# Midas.net
KiCad netlist of a schematic drawn in Altium Designer
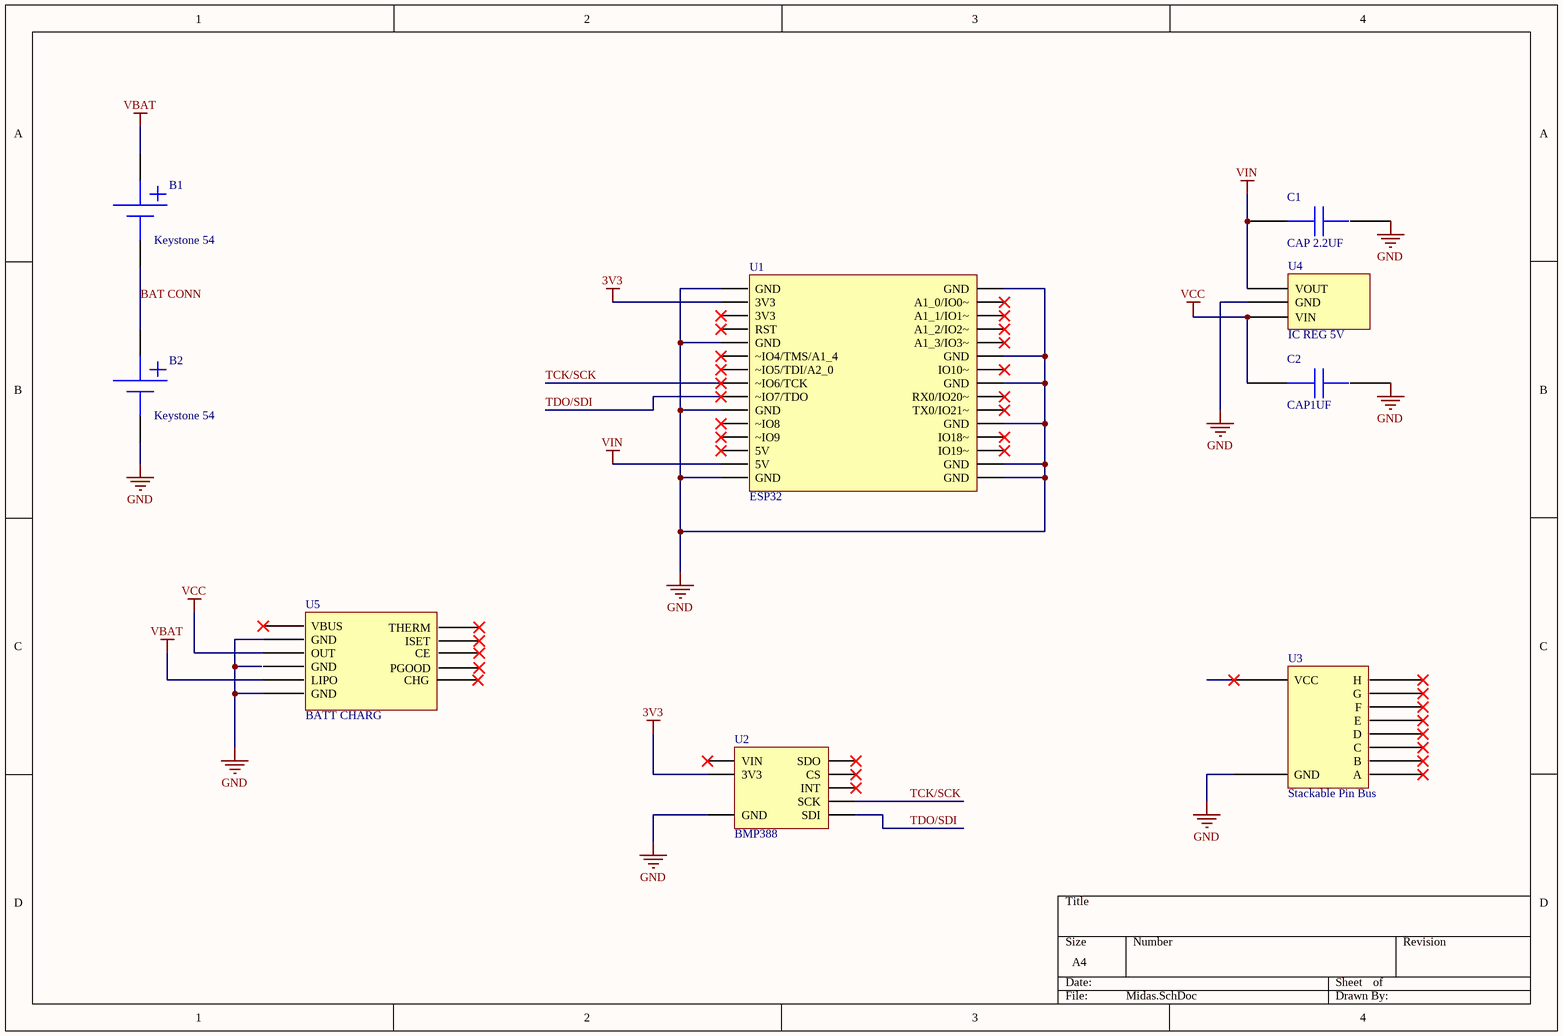
[diagram p0: Midas.SchDoc]

(export (version "E")
  (design (tool "Eeschema 10.0.6"))
  (components
    (comp (ref "B1")
      (value "Keystone 54")
      (footprint "Keystone 54")
      (description "Batteries/Accessories\r\nBATT CONT CLIP 18650 1CEL PC PIN")
      (fields
        (field (name "MANUFACTURER") "Keystone Electronics")
        (field (name "MANUFACTURER PART NUMBER") "54")
      )
      (libsource (lib "Midas") (part "54"))
    )
    (comp (ref "B2")
      (value "Keystone 54")
      (footprint "Keystone 54")
      (description "Batteries/Accessories\r\nBATT CONT CLIP 18650 1CEL PC PIN")
      (fields
        (field (name "MANUFACTURER") "Keystone Electronics")
        (field (name "MANUFACTURER PART NUMBER") "54")
      )
      (libsource (lib "Midas") (part "54"))
    )
    (comp (ref "C1")
      (value "CAP 2.2UF")
      (footprint "FA16X7R1E225KNU06")
      (fields
        (field (name "MANUFACTURER") "TDK")
        (field (name "MANUFACTURER PART NUMBER") "FA16X7R1E225KNU06")
      )
      (libsource (lib "Midas") (part "FA16X7R1E225KNU06"))
    )
    (comp (ref "C2")
      (value "CAP1UF")
      (footprint "C330C105K5R5TA7301")
      (fields
        (field (name "MANUFACTURER") "KEMET")
        (field (name "MANUFACTURER PART NUMBER") "C330C105K5R5TA7301")
      )
      (libsource (lib "Midas") (part "C330C105K5R5TA7301"))
    )
    (comp (ref "U1")
      (value "ESP32")
      (footprint "ESP32")
      (fields
        (field (name "MANUFACTURER") "Espressif Systems")
        (field (name "MANUFACTURER PART NUMBER") "ESP32-C3-DEVKITC-02")
      )
      (libsource (lib "Midas") (part "ESP32-C3-DEVKITC-02"))
    )
    (comp (ref "U2")
      (value "BMP388")
      (footprint "3966")
      (fields
        (field (name "MANUFACTURER") "Adafruit Industries")
        (field (name "MANUFACTURER PART NUMBER") "3966")
      )
      (libsource (lib "Midas") (part "3966"))
    )
    (comp (ref "U3")
      (value "Stackable Pin Bus")
      (footprint "STACKABLE_PIN_BUS")
      (description "10 pinos, Passo 2.54mm, Dimensões da barra 26x2x8mm")
      (libsource (lib "Midas") (part "Barramento Empilhável"))
    )
    (comp (ref "U4")
      (value "IC REG 5V")
      (footprint "AP7381-50V-A")
      (description "Fixed Positive LDO Regulator")
      (fields (field (name "MANUFACTURER") "Diodes") (field (name "MANUFACTURER PART NUMBER") "AP7381-50V-A"))
      (libsource (lib "Midas") (part "AP7381-50V-A"))
    )
    (comp (ref "U5")
      (value "BATT CHARG")
      (footprint "4755")
      (fields
        (field (name "MANUFACTURER") "Adafruit Industries")
        (field (name "MANUFACTURER PART NUMBER") "4755")
      )
      (libsource (lib "Midas") (part "4755"))
    )
  )
  (nets
    (net (code "1") (name "/BAT CONN") (class "Default")
      (node (ref "B1") (pin "2") (pinfunction "NEG_2") (pintype "passive"))
      (node (ref "B2") (pin "1") (pinfunction "POS_1") (pintype "passive"))
    )
    (net (code "2") (name "/TCK{slash}SCK") (class "Default")
      (node (ref "U1") (pin "8") (pinfunction "~IO6/TCK_8") (pintype "passive"))
      (node (ref "U2") (pin "4") (pinfunction "SCK_4") (pintype "passive"))
    )
    (net (code "3") (name "/TDO{slash}SDI") (class "Default")
      (node (ref "U1") (pin "9") (pinfunction "~IO7/TDO_9") (pintype "passive"))
      (node (ref "U2") (pin "6") (pinfunction "SDI_6") (pintype "passive"))
    )
    (net (code "4") (name "3V3") (class "Default")
      (node (ref "U1") (pin "2") (pinfunction "3V3_2") (pintype "passive"))
      (node (ref "U2") (pin "2") (pinfunction "3V3_2") (pintype "passive"))
    )
    (net (code "5") (name "GND") (class "Default")
      (node (ref "B2") (pin "2") (pinfunction "NEG_2") (pintype "passive"))
      (node (ref "C1") (pin "2") (pinfunction "2_2") (pintype "passive"))
      (node (ref "C2") (pin "2") (pinfunction "2_2") (pintype "passive"))
      (node (ref "U1") (pin "1") (pinfunction "GND_1") (pintype "passive"))
      (node (ref "U1") (pin "10") (pinfunction "GND_10") (pintype "passive"))
      (node (ref "U1") (pin "15") (pinfunction "GND_15") (pintype "passive"))
      (node (ref "U1") (pin "16") (pinfunction "GND_16") (pintype "passive"))
      (node (ref "U1") (pin "17") (pinfunction "GND_17") (pintype "passive"))
      (node (ref "U1") (pin "20") (pinfunction "GND_20") (pintype "passive"))
      (node (ref "U1") (pin "23") (pinfunction "GND_23") (pintype "passive"))
      (node (ref "U1") (pin "25") (pinfunction "GND_25") (pintype "passive"))
      (node (ref "U1") (pin "30") (pinfunction "GND_30") (pintype "passive"))
      (node (ref "U1") (pin "5") (pinfunction "GND_5") (pintype "passive"))
      (node (ref "U2") (pin "3") (pinfunction "GND_3") (pintype "passive"))
      (node (ref "U3") (pin "2") (pinfunction "GND_2") (pintype "passive"))
      (node (ref "U4") (pin "2") (pinfunction "GND_2") (pintype "passive"))
      (node (ref "U5") (pin "11") (pinfunction "GND_11") (pintype "passive"))
      (node (ref "U5") (pin "2") (pinfunction "GND_2") (pintype "passive"))
    )
    (net (code "6") (name "VBAT") (class "Default")
      (node (ref "B1") (pin "1") (pinfunction "POS_1") (pintype "passive"))
      (node (ref "U5") (pin "10") (pinfunction "LIPO_10") (pintype "passive"))
    )
    (net (code "7") (name "VCC") (class "Default")
      (node (ref "C2") (pin "1") (pinfunction "1_1") (pintype "passive"))
      (node (ref "U4") (pin "3") (pinfunction "VIN_3") (pintype "passive"))
      (node (ref "U5") (pin "8") (pinfunction "OUT_8") (pintype "passive"))
    )
    (net (code "8") (name "VIN") (class "Default")
      (node (ref "C1") (pin "1") (pinfunction "1_1") (pintype "passive"))
      (node (ref "U1") (pin "14") (pinfunction "5V_14") (pintype "passive"))
      (node (ref "U4") (pin "1") (pinfunction "VOUT_1") (pintype "passive"))
    )
    (net (code "9") (name "unconnected-(U1-3V3-Pad3)") (class "Default")
      (node (ref "U1") (pin "3") (pinfunction "3V3_3") (pintype "passive+no_connect"))
    )
    (net (code "10") (name "unconnected-(U1-5V-Pad13)") (class "Default")
      (node (ref "U1") (pin "13") (pinfunction "5V_13") (pintype "passive+no_connect"))
    )
    (net (code "11") (name "unconnected-(U1-A1_0{slash}IO0~-Pad29)") (class "Default")
      (node (ref "U1") (pin "29") (pinfunction "A1_0/IO0~_29") (pintype "passive+no_connect"))
    )
    (net (code "12") (name "unconnected-(U1-A1_1{slash}IO1~-Pad28)") (class "Default")
      (node (ref "U1") (pin "28") (pinfunction "A1_1/IO1~_28") (pintype "passive+no_connect"))
    )
    (net (code "13") (name "unconnected-(U1-A1_2{slash}IO2~-Pad27)") (class "Default")
      (node (ref "U1") (pin "27") (pinfunction "A1_2/IO2~_27") (pintype "passive+no_connect"))
    )
    (net (code "14") (name "unconnected-(U1-A1_3{slash}IO3~-Pad26)") (class "Default")
      (node (ref "U1") (pin "26") (pinfunction "A1_3/IO3~_26") (pintype "passive+no_connect"))
    )
    (net (code "15") (name "unconnected-(U1-IO10~-Pad24)") (class "Default")
      (node (ref "U1") (pin "24") (pinfunction "IO10~_24") (pintype "passive+no_connect"))
    )
    (net (code "16") (name "unconnected-(U1-IO18~-Pad19)") (class "Default")
      (node (ref "U1") (pin "19") (pinfunction "IO18~_19") (pintype "passive+no_connect"))
    )
    (net (code "17") (name "unconnected-(U1-IO19~-Pad18)") (class "Default")
      (node (ref "U1") (pin "18") (pinfunction "IO19~_18") (pintype "passive+no_connect"))
    )
    (net (code "18") (name "unconnected-(U1-RST-Pad4)") (class "Default")
      (node (ref "U1") (pin "4") (pinfunction "RST_4") (pintype "passive+no_connect"))
    )
    (net (code "19") (name "unconnected-(U1-RX0{slash}IO20~-Pad22)") (class "Default")
      (node (ref "U1") (pin "22") (pinfunction "RX0/IO20~_22") (pintype "passive+no_connect"))
    )
    (net (code "20") (name "unconnected-(U1-TX0{slash}IO21~-Pad21)") (class "Default")
      (node (ref "U1") (pin "21") (pinfunction "TX0/IO21~_21") (pintype "passive+no_connect"))
    )
    (net (code "21") (name "unconnected-(U1-~IO4{slash}TMS{slash}A1_4-Pad6)") (class "Default")
      (node (ref "U1") (pin "6") (pinfunction "~IO4/TMS/A1_4_6") (pintype "passive+no_connect"))
    )
    (net (code "22") (name "unconnected-(U1-~IO5{slash}TDI{slash}A2_0-Pad7)") (class "Default")
      (node (ref "U1") (pin "7") (pinfunction "~IO5/TDI/A2_0_7") (pintype "passive+no_connect"))
    )
    (net (code "23") (name "unconnected-(U1-~IO8-Pad11)") (class "Default")
      (node (ref "U1") (pin "11") (pinfunction "~IO8_11") (pintype "passive+no_connect"))
    )
    (net (code "24") (name "unconnected-(U1-~IO9-Pad12)") (class "Default")
      (node (ref "U1") (pin "12") (pinfunction "~IO9_12") (pintype "passive+no_connect"))
    )
    (net (code "25") (name "unconnected-(U2-CS-Pad7)") (class "Default")
      (node (ref "U2") (pin "7") (pinfunction "CS_7") (pintype "passive+no_connect"))
    )
    (net (code "26") (name "unconnected-(U2-INT-Pad8)") (class "Default")
      (node (ref "U2") (pin "8") (pinfunction "INT_8") (pintype "passive+no_connect"))
    )
    (net (code "27") (name "unconnected-(U2-SDO-Pad5)") (class "Default")
      (node (ref "U2") (pin "5") (pinfunction "SDO_5") (pintype "passive+no_connect"))
    )
    (net (code "28") (name "unconnected-(U2-VIN-Pad1)") (class "Default")
      (node (ref "U2") (pin "1") (pinfunction "VIN_1") (pintype "passive+no_connect"))
    )
    (net (code "29") (name "unconnected-(U3-A-Pad3)") (class "Default")
      (node (ref "U3") (pin "3") (pinfunction "A_3") (pintype "passive+no_connect"))
    )
    (net (code "30") (name "unconnected-(U3-B-Pad4)") (class "Default")
      (node (ref "U3") (pin "4") (pinfunction "B_4") (pintype "passive+no_connect"))
    )
    (net (code "31") (name "unconnected-(U3-C-Pad5)") (class "Default")
      (node (ref "U3") (pin "5") (pinfunction "C_5") (pintype "passive+no_connect"))
    )
    (net (code "32") (name "unconnected-(U3-D-Pad6)") (class "Default")
      (node (ref "U3") (pin "6") (pinfunction "D_6") (pintype "passive+no_connect"))
    )
    (net (code "33") (name "unconnected-(U3-E-Pad7)") (class "Default")
      (node (ref "U3") (pin "7") (pinfunction "E_7") (pintype "passive+no_connect"))
    )
    (net (code "34") (name "unconnected-(U3-F-Pad8)") (class "Default")
      (node (ref "U3") (pin "8") (pinfunction "F_8") (pintype "passive+no_connect"))
    )
    (net (code "35") (name "unconnected-(U3-G-Pad9)") (class "Default")
      (node (ref "U3") (pin "9") (pinfunction "G_9") (pintype "passive+no_connect"))
    )
    (net (code "36") (name "unconnected-(U3-H-Pad10)") (class "Default")
      (node (ref "U3") (pin "10") (pinfunction "H_10") (pintype "passive+no_connect"))
    )
    (net (code "37") (name "unconnected-(U3-VCC-Pad1)") (class "Default")
      (node (ref "U3") (pin "1") (pinfunction "VCC_1") (pintype "passive+no_connect"))
    )
    (net (code "38") (name "unconnected-(U5-CE-Pad5)") (class "Default")
      (node (ref "U5") (pin "5") (pinfunction "CE_5") (pintype "passive+no_connect"))
    )
    (net (code "39") (name "unconnected-(U5-CHG-Pad7)") (class "Default")
      (node (ref "U5") (pin "7") (pinfunction "CHG_7") (pintype "passive+no_connect"))
    )
    (net (code "40") (name "unconnected-(U5-GND-Pad9)") (class "Default")
      (node (ref "U5") (pin "9") (pinfunction "GND_9") (pintype "passive"))
    )
    (net (code "41") (name "unconnected-(U5-ISET-Pad4)") (class "Default")
      (node (ref "U5") (pin "4") (pinfunction "ISET_4") (pintype "passive+no_connect"))
    )
    (net (code "42") (name "unconnected-(U5-PGOOD-Pad6)") (class "Default")
      (node (ref "U5") (pin "6") (pinfunction "PGOOD_6") (pintype "passive+no_connect"))
    )
    (net (code "43") (name "unconnected-(U5-THERM-Pad3)") (class "Default")
      (node (ref "U5") (pin "3") (pinfunction "THERM_3") (pintype "passive+no_connect"))
    )
    (net (code "44") (name "unconnected-(U5-VBUS-Pad1)") (class "Default")
      (node (ref "U5") (pin "1") (pinfunction "VBUS_1") (pintype "passive+no_connect"))
    )
  )
)
